# Sheet1.net
KiCad netlist of a schematic drawn in Altium Designer
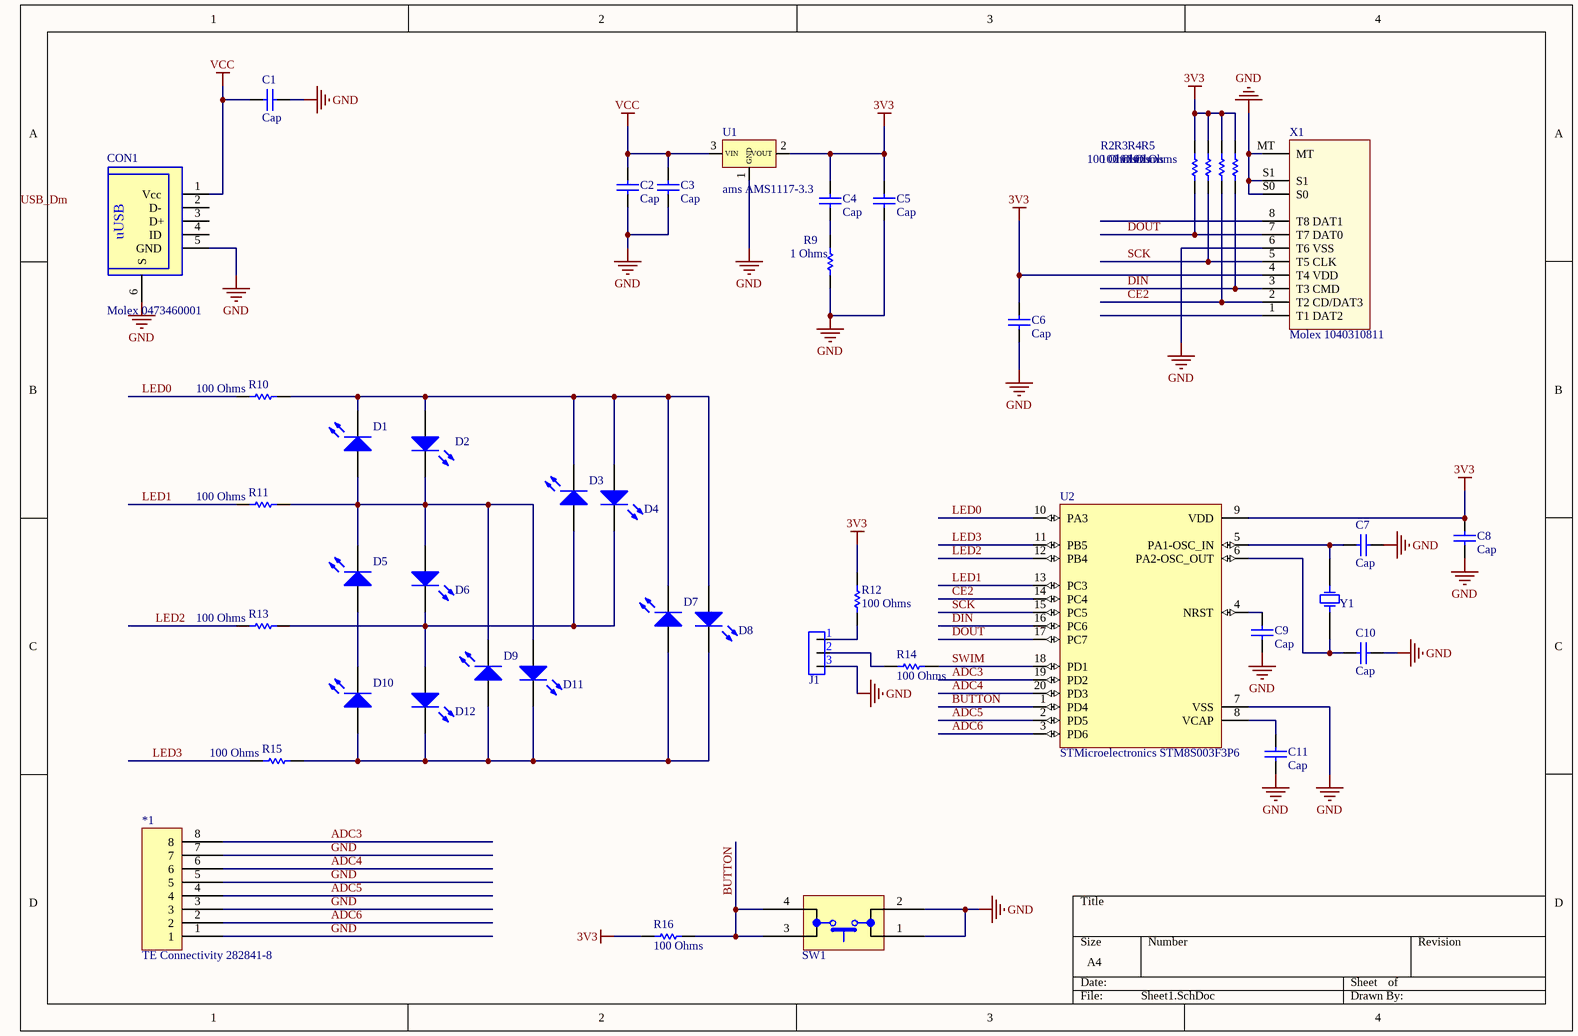
[diagram p0: Sheet1.SchDoc]

(export (version "E")
  (design (tool "Eeschema 10.0.6"))
  (components
    (comp (ref "*1")
      (value "TE Connectivity 282841-8")
      (footprint "PCB-5n16zmdo33ly3n5be8x4-1")
      (description "Buchanan; Conn; Term Blk; PCB; 8; 5.08 mm; 30-12 AWG; Green; 17.5 A; 300 V")
      (fields (field (name "MANUFACTURER PART NUMBER") "282841-8"))
      (libsource (lib "FavoritesLibrary") (part "SYM-0b4dc01c7a6bd48a-1"))
    )
    (comp (ref "C1")
      (value "Cap")
      (footprint "0805_SMD_CAP")
      (description "CMS Capacitor")
      (libsource (lib "CommunityVault") (part "SYM-154cdccdb346ca8b-1"))
    )
    (comp (ref "C2")
      (value "Cap")
      (footprint "0805_SMD_CAP")
      (description "CMS Capacitor")
      (libsource (lib "CommunityVault") (part "SYM-154cdccdb346ca8b-1"))
    )
    (comp (ref "C3")
      (value "Cap")
      (footprint "0805_SMD_CAP")
      (description "CMS Capacitor")
      (libsource (lib "CommunityVault") (part "SYM-154cdccdb346ca8b-1"))
    )
    (comp (ref "C4")
      (value "Cap")
      (footprint "0805_SMD_CAP")
      (description "CMS Capacitor")
      (libsource (lib "CommunityVault") (part "SYM-154cdccdb346ca8b-1"))
    )
    (comp (ref "C5")
      (value "Cap")
      (footprint "0805_SMD_CAP")
      (description "CMS Capacitor")
      (libsource (lib "CommunityVault") (part "SYM-154cdccdb346ca8b-1"))
    )
    (comp (ref "C6")
      (value "Cap")
      (footprint "0805_SMD_CAP")
      (description "CMS Capacitor")
      (libsource (lib "CommunityVault") (part "SYM-154cdccdb346ca8b-1"))
    )
    (comp (ref "C7")
      (value "Cap")
      (footprint "0805_SMD_CAP")
      (description "CMS Capacitor")
      (libsource (lib "CommunityVault") (part "SYM-154cdccdb346ca8b-1"))
    )
    (comp (ref "C8")
      (value "Cap")
      (footprint "0805_SMD_CAP")
      (description "CMS Capacitor")
      (libsource (lib "CommunityVault") (part "SYM-154cdccdb346ca8b-1"))
    )
    (comp (ref "C9")
      (value "Cap")
      (footprint "0805_SMD_CAP")
      (description "CMS Capacitor")
      (libsource (lib "CommunityVault") (part "SYM-154cdccdb346ca8b-1"))
    )
    (comp (ref "C10")
      (value "Cap")
      (footprint "0805_SMD_CAP")
      (description "CMS Capacitor")
      (libsource (lib "CommunityVault") (part "SYM-154cdccdb346ca8b-1"))
    )
    (comp (ref "C11")
      (value "Cap")
      (footprint "0805_SMD_CAP")
      (description "CMS Capacitor")
      (libsource (lib "CommunityVault") (part "SYM-154cdccdb346ca8b-1"))
    )
    (comp (ref "CON1")
      (value "Molex 0473460001")
      (footprint "PCB-2328464-1")
      (description "Conn Micro USB Type B RCP 5 POS 0.65mm Solder RA SMD 5 Terminal 1 Port Embossed T/R")
      (libsource (lib "FavoritesLibrary") (part "SYM-2328464-1"))
    )
    (comp (ref "D1")
      (value "Avago HLMP-1700")
      (footprint "PCB-i0lu3ywj2mjd0tfwcgvk-1")
      (description "Red 3 mm 50° Tinted Diffused 2 mcd 1.8 V Solid State LED Lamp Through Hole")
      (fields (field (name "MANUFACTURER PART NUMBER") "HLMP-1700"))
      (libsource (lib "FavoritesLibrary") (part "SYM-93ac5aa6a05f4c6b-1"))
    )
    (comp (ref "D2")
      (value "Avago HLMP-1700")
      (footprint "PCB-i0lu3ywj2mjd0tfwcgvk-1")
      (description "Red 3 mm 50° Tinted Diffused 2 mcd 1.8 V Solid State LED Lamp Through Hole")
      (fields (field (name "MANUFACTURER PART NUMBER") "HLMP-1700"))
      (libsource (lib "FavoritesLibrary") (part "SYM-93ac5aa6a05f4c6b-1"))
    )
    (comp (ref "D3")
      (value "Avago HLMP-1700")
      (footprint "PCB-i0lu3ywj2mjd0tfwcgvk-1")
      (description "Red 3 mm 50° Tinted Diffused 2 mcd 1.8 V Solid State LED Lamp Through Hole")
      (fields (field (name "MANUFACTURER PART NUMBER") "HLMP-1700"))
      (libsource (lib "FavoritesLibrary") (part "SYM-93ac5aa6a05f4c6b-1"))
    )
    (comp (ref "D4")
      (value "Avago HLMP-1700")
      (footprint "PCB-i0lu3ywj2mjd0tfwcgvk-1")
      (description "Red 3 mm 50° Tinted Diffused 2 mcd 1.8 V Solid State LED Lamp Through Hole")
      (fields (field (name "MANUFACTURER PART NUMBER") "HLMP-1700"))
      (libsource (lib "FavoritesLibrary") (part "SYM-93ac5aa6a05f4c6b-1"))
    )
    (comp (ref "D5")
      (value "Avago HLMP-1700")
      (footprint "PCB-i0lu3ywj2mjd0tfwcgvk-1")
      (description "Red 3 mm 50° Tinted Diffused 2 mcd 1.8 V Solid State LED Lamp Through Hole")
      (fields (field (name "MANUFACTURER PART NUMBER") "HLMP-1700"))
      (libsource (lib "FavoritesLibrary") (part "SYM-93ac5aa6a05f4c6b-1"))
    )
    (comp (ref "D6")
      (value "Avago HLMP-1700")
      (footprint "PCB-i0lu3ywj2mjd0tfwcgvk-1")
      (description "Red 3 mm 50° Tinted Diffused 2 mcd 1.8 V Solid State LED Lamp Through Hole")
      (fields (field (name "MANUFACTURER PART NUMBER") "HLMP-1700"))
      (libsource (lib "FavoritesLibrary") (part "SYM-93ac5aa6a05f4c6b-1"))
    )
    (comp (ref "D7")
      (value "Avago HLMP-1700")
      (footprint "PCB-i0lu3ywj2mjd0tfwcgvk-1")
      (description "Red 3 mm 50° Tinted Diffused 2 mcd 1.8 V Solid State LED Lamp Through Hole")
      (fields (field (name "MANUFACTURER PART NUMBER") "HLMP-1700"))
      (libsource (lib "FavoritesLibrary") (part "SYM-93ac5aa6a05f4c6b-1"))
    )
    (comp (ref "D8")
      (value "Avago HLMP-1700")
      (footprint "PCB-i0lu3ywj2mjd0tfwcgvk-1")
      (description "Red 3 mm 50° Tinted Diffused 2 mcd 1.8 V Solid State LED Lamp Through Hole")
      (fields (field (name "MANUFACTURER PART NUMBER") "HLMP-1700"))
      (libsource (lib "FavoritesLibrary") (part "SYM-93ac5aa6a05f4c6b-1"))
    )
    (comp (ref "D9")
      (value "Avago HLMP-1700")
      (footprint "PCB-i0lu3ywj2mjd0tfwcgvk-1")
      (description "Red 3 mm 50° Tinted Diffused 2 mcd 1.8 V Solid State LED Lamp Through Hole")
      (fields (field (name "MANUFACTURER PART NUMBER") "HLMP-1700"))
      (libsource (lib "FavoritesLibrary") (part "SYM-93ac5aa6a05f4c6b-1"))
    )
    (comp (ref "D10")
      (value "Avago HLMP-1700")
      (footprint "PCB-i0lu3ywj2mjd0tfwcgvk-1")
      (description "Red 3 mm 50° Tinted Diffused 2 mcd 1.8 V Solid State LED Lamp Through Hole")
      (fields (field (name "MANUFACTURER PART NUMBER") "HLMP-1700"))
      (libsource (lib "FavoritesLibrary") (part "SYM-93ac5aa6a05f4c6b-1"))
    )
    (comp (ref "D11")
      (value "Avago HLMP-1700")
      (footprint "PCB-i0lu3ywj2mjd0tfwcgvk-1")
      (description "Red 3 mm 50° Tinted Diffused 2 mcd 1.8 V Solid State LED Lamp Through Hole")
      (fields (field (name "MANUFACTURER PART NUMBER") "HLMP-1700"))
      (libsource (lib "FavoritesLibrary") (part "SYM-93ac5aa6a05f4c6b-1"))
    )
    (comp (ref "D12")
      (value "Avago HLMP-1700")
      (footprint "PCB-i0lu3ywj2mjd0tfwcgvk-1")
      (description "Red 3 mm 50° Tinted Diffused 2 mcd 1.8 V Solid State LED Lamp Through Hole")
      (fields (field (name "MANUFACTURER PART NUMBER") "HLMP-1700"))
      (libsource (lib "FavoritesLibrary") (part "SYM-93ac5aa6a05f4c6b-1"))
    )
    (comp (ref "J1")
      (value "Sensor Temperatura - Final")
      (footprint "PCB-vkgeqjtjqx6hhmcxuagx-1")
      (description "AMPMODU 3 Position 2.54 mm Single Row Through-Hole Straight Breakaway Header")
      (fields (field (name "MANUFACTURER PART NUMBER") "5-146274-3"))
      (libsource (lib "FavoritesLibrary") (part "SYM-52d299a8d8748d15-1"))
    )
    (comp (ref "R2")
      (value "100 Ohms")
      (footprint "RESC2013X70X40LL20T20")
      (description "Thick Film Resistors - SMD 0805 100Ohms 5% Tolerance")
      (libsource (lib "CommunityVault") (part "CMP-3683550-2"))
    )
    (comp (ref "R3")
      (value "100 Ohms")
      (footprint "RESC2013X70X40LL20T20")
      (description "Thick Film Resistors - SMD 0805 100Ohms 5% Tolerance")
      (libsource (lib "CommunityVault") (part "CMP-3683550-2"))
    )
    (comp (ref "R4")
      (value "100 Ohms")
      (footprint "RESC2013X70X40LL20T20")
      (description "Thick Film Resistors - SMD 0805 100Ohms 5% Tolerance")
      (libsource (lib "CommunityVault") (part "CMP-3683550-2"))
    )
    (comp (ref "R5")
      (value "100 Ohms")
      (footprint "RESC2013X70X40LL20T20")
      (description "Thick Film Resistors - SMD 0805 100Ohms 5% Tolerance")
      (libsource (lib "CommunityVault") (part "CMP-3683550-2"))
    )
    (comp (ref "R9")
      (value "1 Ohms")
      (footprint "RESC2013X70X40LL20T20")
      (description "Thick Film Resistors - SMD 0805 100Ohms 5% Tolerance")
      (libsource (lib "CommunityVault") (part "CMP-3683550-2"))
    )
    (comp (ref "R10")
      (value "100 Ohms")
      (footprint "RESC2013X70X40LL20T20")
      (description "Thick Film Resistors - SMD 0805 100Ohms 5% Tolerance")
      (libsource (lib "CommunityVault") (part "CMP-3683550-2"))
    )
    (comp (ref "R11")
      (value "100 Ohms")
      (footprint "RESC2013X70X40LL20T20")
      (description "Thick Film Resistors - SMD 0805 100Ohms 5% Tolerance")
      (libsource (lib "CommunityVault") (part "CMP-3683550-2"))
    )
    (comp (ref "R12")
      (value "100 Ohms")
      (footprint "RESC2013X70X40LL20T20")
      (description "Thick Film Resistors - SMD 0805 100Ohms 5% Tolerance")
      (libsource (lib "CommunityVault") (part "CMP-3683550-2"))
    )
    (comp (ref "R13")
      (value "100 Ohms")
      (footprint "RESC2013X70X40LL20T20")
      (description "Thick Film Resistors - SMD 0805 100Ohms 5% Tolerance")
      (libsource (lib "CommunityVault") (part "CMP-3683550-2"))
    )
    (comp (ref "R14")
      (value "100 Ohms")
      (footprint "RESC2013X70X40LL20T20")
      (description "Thick Film Resistors - SMD 0805 100Ohms 5% Tolerance")
      (libsource (lib "CommunityVault") (part "CMP-3683550-2"))
    )
    (comp (ref "R15")
      (value "100 Ohms")
      (footprint "RESC2013X70X40LL20T20")
      (description "Thick Film Resistors - SMD 0805 100Ohms 5% Tolerance")
      (libsource (lib "CommunityVault") (part "CMP-3683550-2"))
    )
    (comp (ref "R16")
      (value "100 Ohms")
      (footprint "RESC2013X70X40LL20T20")
      (description "Thick Film Resistors - SMD 0805 100Ohms 5% Tolerance")
      (libsource (lib "CommunityVault") (part "CMP-3683550-2"))
    )
    (comp (ref "SW1")
      (value "TE Connectivity / AMP 1825910-6")
      (footprint "PCB-gaic1pl4705ifv3nefaq-1")
      (description "Switch Tactile OFF (ON) SPST Round Button PC Pins 0.05A 24VDC 100000Cycles 1.57N Thru-Hole Loose")
      (fields (field (name "MANUFACTURER PART NUMBER") "1825910-6"))
      (libsource (lib "CommunityVault") (part "CMP-3ee8f78971b1e12f-10"))
    )
    (comp (ref "U1")
      (value "ams AMS1117-3.3")
      (footprint "MP04A_N")
      (description "Sot223/Pkg 1-Amp 3.3-Volt Low Drop Out Voltage Regulatator")
      (fields (field (name "MANUFACTURER PART NUMBER") "AMS1117-3.3"))
      (libsource (lib "FavoritesLibrary") (part "SYM-3fd1f74ee88ee016-1"))
    )
    (comp (ref "U2")
      (value "STMicroelectronics STM8S003F3P6")
      (footprint "PCB-3782863-1")
      (description "IC MCU 8BIT 8KB FLASH 20TSSOP")
      (libsource (lib "CommunityVault") (part "CMP-3782863-3"))
    )
    (comp (ref "X1")
      (value "Molex 1040310811")
      (footprint "PCB-e07cv7eyfg1wxdj7ioop-1")
      (description "1.10mm Pitch microSD Memory Card Connector, SMT, Push-Pull Type, 1.42mm Height, with Detect Switch")
      (fields (field (name "MANUFACTURER PART NUMBER") "1040310811"))
      (libsource (lib "FavoritesLibrary") (part "SYM-2b5fe340ab7ff498-1"))
    )
    (comp (ref "Y1")
      (value "Fox Electronics FOXSLF/080-20")
      (footprint "HC49")
      (description "CRYSTAL 8.0MHZ 20PF THRU")
      (libsource (lib "FavoritesLibrary") (part "SYM-783541-1"))
    )
  )
  (nets
    (net (code "1") (name "/ADC3") (class "Default")
      (node (ref "*1") (pin "8") (pinfunction "8_8") (pintype "passive"))
      (node (ref "U2") (pin "19") (pinfunction "PD2_19") (pintype "bidirectional"))
    )
    (net (code "2") (name "/ADC4") (class "Default")
      (node (ref "*1") (pin "6") (pinfunction "6_6") (pintype "passive"))
      (node (ref "U2") (pin "20") (pinfunction "PD3_20") (pintype "bidirectional"))
    )
    (net (code "3") (name "/ADC5") (class "Default")
      (node (ref "*1") (pin "4") (pinfunction "4_4") (pintype "passive"))
      (node (ref "U2") (pin "2") (pinfunction "PD5_2") (pintype "bidirectional"))
    )
    (net (code "4") (name "/ADC6") (class "Default")
      (node (ref "*1") (pin "2") (pinfunction "2_2") (pintype "passive"))
      (node (ref "U2") (pin "3") (pinfunction "PD6_3") (pintype "bidirectional"))
    )
    (net (code "5") (name "/BUTTON") (class "Default")
      (node (ref "R16") (pin "1") (pinfunction "1_1") (pintype "passive"))
      (node (ref "SW1") (pin "3") (pinfunction "3_3") (pintype "passive"))
      (node (ref "SW1") (pin "4") (pinfunction "4_4") (pintype "passive"))
      (node (ref "U2") (pin "1") (pinfunction "PD4_1") (pintype "bidirectional"))
    )
    (net (code "6") (name "/CE2") (class "Default")
      (node (ref "R4") (pin "1") (pinfunction "1_1") (pintype "passive"))
      (node (ref "U2") (pin "14") (pinfunction "PC4_14") (pintype "bidirectional"))
      (node (ref "X1") (pin "2") (pinfunction "T2_CD/DAT3_2") (pintype "passive"))
    )
    (net (code "7") (name "/DIN") (class "Default")
      (node (ref "R5") (pin "1") (pinfunction "1_1") (pintype "passive"))
      (node (ref "U2") (pin "16") (pinfunction "PC6_16") (pintype "bidirectional"))
      (node (ref "X1") (pin "3") (pinfunction "T3_CMD_3") (pintype "passive"))
    )
    (net (code "8") (name "/DOUT") (class "Default")
      (node (ref "R2") (pin "1") (pinfunction "1_1") (pintype "passive"))
      (node (ref "U2") (pin "17") (pinfunction "PC7_17") (pintype "bidirectional"))
      (node (ref "X1") (pin "7") (pinfunction "T7_DAT0_7") (pintype "passive"))
    )
    (net (code "9") (name "/LED0") (class "Default")
      (node (ref "R10") (pin "1") (pinfunction "1_1") (pintype "passive"))
      (node (ref "U2") (pin "10") (pinfunction "PA3_10") (pintype "bidirectional"))
    )
    (net (code "10") (name "/LED1") (class "Default")
      (node (ref "R11") (pin "1") (pinfunction "1_1") (pintype "passive"))
      (node (ref "U2") (pin "13") (pinfunction "PC3_13") (pintype "bidirectional"))
    )
    (net (code "11") (name "/LED2") (class "Default")
      (node (ref "R13") (pin "1") (pinfunction "1_1") (pintype "passive"))
      (node (ref "U2") (pin "12") (pinfunction "PB4_12") (pintype "bidirectional"))
    )
    (net (code "12") (name "/LED3") (class "Default")
      (node (ref "R15") (pin "1") (pinfunction "1_1") (pintype "passive"))
      (node (ref "U2") (pin "11") (pinfunction "PB5_11") (pintype "bidirectional"))
    )
    (net (code "13") (name "/SCK") (class "Default")
      (node (ref "R3") (pin "1") (pinfunction "1_1") (pintype "passive"))
      (node (ref "U2") (pin "15") (pinfunction "PC5_15") (pintype "bidirectional"))
      (node (ref "X1") (pin "5") (pinfunction "T5_CLK_5") (pintype "passive"))
    )
    (net (code "14") (name "/SWIM") (class "Default")
      (node (ref "R14") (pin "1") (pinfunction "1_1") (pintype "passive"))
      (node (ref "U2") (pin "18") (pinfunction "PD1_18") (pintype "bidirectional"))
    )
    (net (code "16") (name "3V3") (class "Default")
      (node (ref "C4") (pin "1") (pinfunction "1_1") (pintype "passive"))
      (node (ref "C5") (pin "1") (pinfunction "1_1") (pintype "passive"))
      (node (ref "C6") (pin "2") (pinfunction "2_2") (pintype "passive"))
      (node (ref "C8") (pin "2") (pinfunction "2_2") (pintype "passive"))
      (node (ref "R12") (pin "2") (pinfunction "2_2") (pintype "passive"))
      (node (ref "R16") (pin "2") (pinfunction "2_2") (pintype "passive"))
      (node (ref "R2") (pin "2") (pinfunction "2_2") (pintype "passive"))
      (node (ref "R3") (pin "2") (pinfunction "2_2") (pintype "passive"))
      (node (ref "R4") (pin "2") (pinfunction "2_2") (pintype "passive"))
      (node (ref "R5") (pin "2") (pinfunction "2_2") (pintype "passive"))
      (node (ref "U1") (pin "2") (pinfunction "VOUT_2") (pintype "passive"))
      (node (ref "U2") (pin "9") (pinfunction "VDD_9") (pintype "power_in"))
      (node (ref "X1") (pin "4") (pinfunction "T4_VDD_4") (pintype "passive"))
    )
    (net (code "17") (name "GND") (class "Default")
      (node (ref "*1") (pin "1") (pinfunction "1_1") (pintype "passive"))
      (node (ref "*1") (pin "3") (pinfunction "3_3") (pintype "passive"))
      (node (ref "*1") (pin "5") (pinfunction "5_5") (pintype "passive"))
      (node (ref "*1") (pin "7") (pinfunction "7_7") (pintype "passive"))
      (node (ref "C1") (pin "1") (pinfunction "1_1") (pintype "passive"))
      (node (ref "C10") (pin "1") (pinfunction "1_1") (pintype "passive"))
      (node (ref "C11") (pin "1") (pinfunction "1_1") (pintype "passive"))
      (node (ref "C2") (pin "2") (pinfunction "2_2") (pintype "passive"))
      (node (ref "C3") (pin "2") (pinfunction "2_2") (pintype "passive"))
      (node (ref "C5") (pin "2") (pinfunction "2_2") (pintype "passive"))
      (node (ref "C6") (pin "1") (pinfunction "1_1") (pintype "passive"))
      (node (ref "C7") (pin "1") (pinfunction "1_1") (pintype "passive"))
      (node (ref "C8") (pin "1") (pinfunction "1_1") (pintype "passive"))
      (node (ref "C9") (pin "1") (pinfunction "1_1") (pintype "passive"))
      (node (ref "CON1") (pin "5") (pinfunction "GND_5") (pintype "power_in"))
      (node (ref "CON1") (pin "6") (pinfunction "S_6") (pintype "power_in"))
      (node (ref "J1") (pin "3") (pinfunction "3_3") (pintype "passive"))
      (node (ref "R9") (pin "1") (pinfunction "1_1") (pintype "passive"))
      (node (ref "SW1") (pin "1") (pinfunction "1_1") (pintype "passive"))
      (node (ref "SW1") (pin "2") (pinfunction "2_2") (pintype "passive"))
      (node (ref "U1") (pin "1") (pinfunction "GND_1") (pintype "passive"))
      (node (ref "U2") (pin "7") (pinfunction "VSS_7") (pintype "power_in"))
      (node (ref "X1") (pin "6") (pinfunction "T6_VSS_6") (pintype "passive"))
      (node (ref "X1") (pin "MT") (pinfunction "MT_MT") (pintype "passive"))
      (node (ref "X1") (pin "S0") (pinfunction "S0_S0") (pintype "passive"))
      (node (ref "X1") (pin "S1") (pinfunction "S1_S1") (pintype "passive"))
    )
    (net (code "18") (name "Net-(C4-Pad2)") (class "Default")
      (node (ref "C4") (pin "2") (pinfunction "2_2") (pintype "passive"))
      (node (ref "R9") (pin "2") (pinfunction "2_2") (pintype "passive"))
    )
    (net (code "19") (name "Net-(D1-A)") (class "Default")
      (node (ref "D1") (pin "1") (pinfunction "A_1") (pintype "passive"))
      (node (ref "D11") (pin "1") (pinfunction "A_1") (pintype "passive"))
      (node (ref "D2") (pin "2") (pinfunction "K_2") (pintype "passive"))
      (node (ref "D5") (pin "2") (pinfunction "K_2") (pintype "passive"))
      (node (ref "D6") (pin "1") (pinfunction "A_1") (pintype "passive"))
      (node (ref "D9") (pin "2") (pinfunction "K_2") (pintype "passive"))
      (node (ref "R11") (pin "2") (pinfunction "2_2") (pintype "passive"))
    )
    (net (code "20") (name "Net-(D1-K)") (class "Default")
      (node (ref "D1") (pin "2") (pinfunction "K_2") (pintype "passive"))
      (node (ref "D2") (pin "1") (pinfunction "A_1") (pintype "passive"))
      (node (ref "D3") (pin "2") (pinfunction "K_2") (pintype "passive"))
      (node (ref "D4") (pin "1") (pinfunction "A_1") (pintype "passive"))
      (node (ref "D7") (pin "2") (pinfunction "K_2") (pintype "passive"))
      (node (ref "D8") (pin "1") (pinfunction "A_1") (pintype "passive"))
      (node (ref "R10") (pin "2") (pinfunction "2_2") (pintype "passive"))
    )
    (net (code "21") (name "Net-(D10-A)") (class "Default")
      (node (ref "D10") (pin "1") (pinfunction "A_1") (pintype "passive"))
      (node (ref "D11") (pin "2") (pinfunction "K_2") (pintype "passive"))
      (node (ref "D12") (pin "2") (pinfunction "K_2") (pintype "passive"))
      (node (ref "D7") (pin "1") (pinfunction "A_1") (pintype "passive"))
      (node (ref "D8") (pin "2") (pinfunction "K_2") (pintype "passive"))
      (node (ref "D9") (pin "1") (pinfunction "A_1") (pintype "passive"))
      (node (ref "R15") (pin "2") (pinfunction "2_2") (pintype "passive"))
    )
    (net (code "22") (name "Net-(D10-K)") (class "Default")
      (node (ref "D10") (pin "2") (pinfunction "K_2") (pintype "passive"))
      (node (ref "D5") (pin "1") (pinfunction "A_1") (pintype "passive"))
    )
    (net (code "23") (name "Net-(D12-A)") (class "Default")
      (node (ref "D12") (pin "1") (pinfunction "A_1") (pintype "passive"))
      (node (ref "D3") (pin "1") (pinfunction "A_1") (pintype "passive"))
      (node (ref "D4") (pin "2") (pinfunction "K_2") (pintype "passive"))
      (node (ref "D6") (pin "2") (pinfunction "K_2") (pintype "passive"))
      (node (ref "R13") (pin "2") (pinfunction "2_2") (pintype "passive"))
    )
    (net (code "24") (name "Net-(J1-Pad1)") (class "Default")
      (node (ref "J1") (pin "1") (pinfunction "1_1") (pintype "passive"))
      (node (ref "R12") (pin "1") (pinfunction "1_1") (pintype "passive"))
    )
    (net (code "25") (name "Net-(J1-Pad2)") (class "Default")
      (node (ref "J1") (pin "2") (pinfunction "2_2") (pintype "passive"))
      (node (ref "R14") (pin "2") (pinfunction "2_2") (pintype "passive"))
    )
    (net (code "26") (name "Net-(U2-NRST)") (class "Default")
      (node (ref "C9") (pin "2") (pinfunction "2_2") (pintype "passive"))
      (node (ref "U2") (pin "4") (pinfunction "NRST_4") (pintype "bidirectional"))
    )
    (net (code "27") (name "Net-(U2-PA1-OSC_IN)") (class "Default")
      (node (ref "C7") (pin "2") (pinfunction "2_2") (pintype "passive"))
      (node (ref "U2") (pin "5") (pinfunction "PA1-OSC_IN_5") (pintype "bidirectional"))
      (node (ref "Y1") (pin "2") (pinfunction "2_2") (pintype "passive"))
    )
    (net (code "28") (name "Net-(U2-PA2-OSC_OUT)") (class "Default")
      (node (ref "C10") (pin "2") (pinfunction "2_2") (pintype "passive"))
      (node (ref "U2") (pin "6") (pinfunction "PA2-OSC_OUT_6") (pintype "bidirectional"))
      (node (ref "Y1") (pin "1") (pinfunction "1_1") (pintype "passive"))
    )
    (net (code "29") (name "Net-(U2-VCAP)") (class "Default")
      (node (ref "C11") (pin "2") (pinfunction "2_2") (pintype "passive"))
      (node (ref "U2") (pin "8") (pinfunction "VCAP_8") (pintype "power_in"))
    )
    (net (code "30") (name "VCC") (class "Default")
      (node (ref "C1") (pin "2") (pinfunction "2_2") (pintype "passive"))
      (node (ref "C2") (pin "1") (pinfunction "1_1") (pintype "passive"))
      (node (ref "C3") (pin "1") (pinfunction "1_1") (pintype "passive"))
      (node (ref "CON1") (pin "1") (pinfunction "Vcc_1") (pintype "power_in"))
      (node (ref "U1") (pin "3") (pinfunction "VIN_3") (pintype "passive"))
    )
    (net (code "31") (name "unconnected-(CON1-D+-Pad3)") (class "Default")
      (node (ref "CON1") (pin "3") (pinfunction "D+_3") (pintype "power_in"))
    )
    (net (code "32") (name "unconnected-(CON1-D--Pad2)") (class "Default")
      (node (ref "CON1") (pin "2") (pinfunction "D-_2") (pintype "power_in"))
    )
    (net (code "33") (name "unconnected-(CON1-ID-Pad4)") (class "Default")
      (node (ref "CON1") (pin "4") (pinfunction "ID_4") (pintype "power_in"))
    )
    (net (code "34") (name "unconnected-(X1-T1_DAT2-Pad1)") (class "Default")
      (node (ref "X1") (pin "1") (pinfunction "T1_DAT2_1") (pintype "passive"))
    )
    (net (code "35") (name "unconnected-(X1-T8_DAT1-Pad8)") (class "Default")
      (node (ref "X1") (pin "8") (pinfunction "T8_DAT1_8") (pintype "passive"))
    )
  )
)
